# untitled.net
KiCad netlist of a schematic drawn in EAGLE
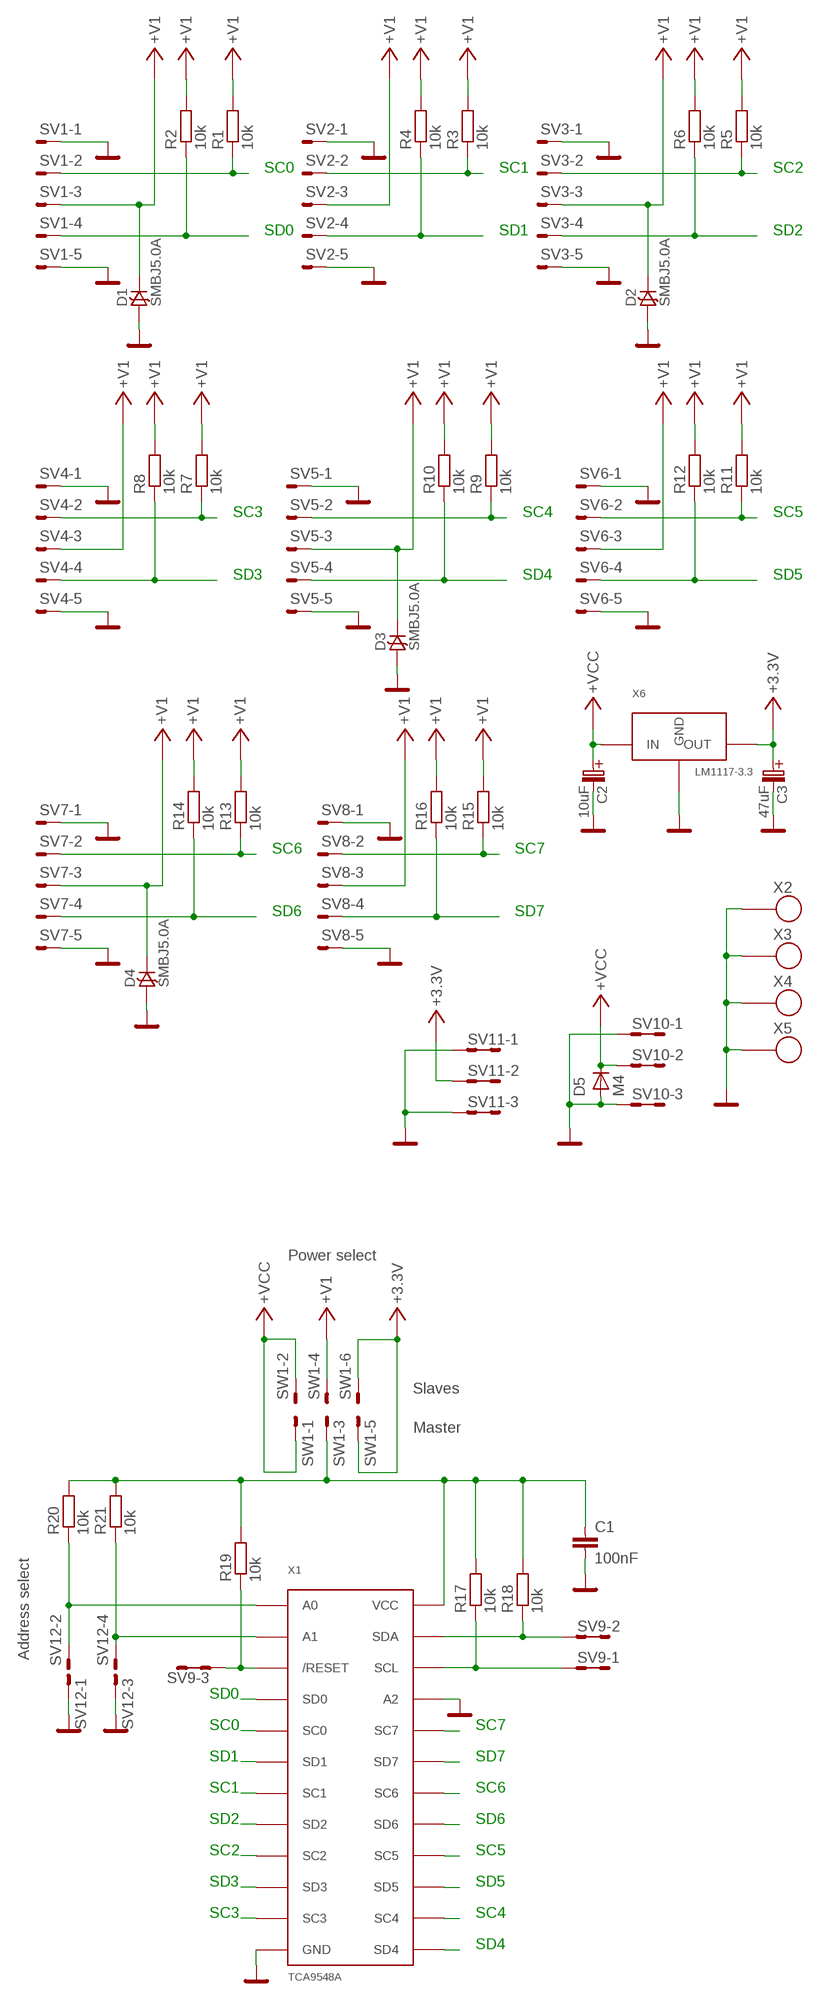
[diagram p0: schematic, sheet 1]

(export (version "E")
  (design (tool "Eeschema 10.0.6"))
  (components
    (comp (ref "C1")
      (value "100nF")
      (footprint "eagle-import:C0805")
      (libsource (lib "eagle-import") (part "C0805"))
    )
    (comp (ref "C2") (value "10uF") (footprint "eagle-import:B") (libsource (lib "eagle-import") (part "B")))
    (comp (ref "C3") (value "47uF") (footprint "eagle-import:C") (libsource (lib "eagle-import") (part "C")))
    (comp (ref "D1")
      (value "SMBJ5.0A")
      (footprint "eagle-import:SMA")
      (libsource (lib "eagle-import") (part "D-TRANSIL-SMA"))
    )
    (comp (ref "D2")
      (value "SMBJ5.0A")
      (footprint "eagle-import:SMA")
      (libsource (lib "eagle-import") (part "D-TRANSIL-SMA"))
    )
    (comp (ref "D3")
      (value "SMBJ5.0A")
      (footprint "eagle-import:SMA")
      (libsource (lib "eagle-import") (part "D-TRANSIL-SMA"))
    )
    (comp (ref "D4")
      (value "SMBJ5.0A")
      (footprint "eagle-import:SMA")
      (libsource (lib "eagle-import") (part "D-TRANSIL-SMA"))
    )
    (comp (ref "D5")
      (value "M4")
      (footprint "eagle-import:SMA")
      (libsource (lib "eagle-import") (part "D-OB.SMA"))
    )
    (comp (ref "R1")
      (value "10k")
      (footprint "eagle-import:0805")
      (libsource (lib "eagle-import") (part "R0805"))
    )
    (comp (ref "R2")
      (value "10k")
      (footprint "eagle-import:0805")
      (libsource (lib "eagle-import") (part "R0805"))
    )
    (comp (ref "R3")
      (value "10k")
      (footprint "eagle-import:0805")
      (libsource (lib "eagle-import") (part "R0805"))
    )
    (comp (ref "R4")
      (value "10k")
      (footprint "eagle-import:0805")
      (libsource (lib "eagle-import") (part "R0805"))
    )
    (comp (ref "R5")
      (value "10k")
      (footprint "eagle-import:0805")
      (libsource (lib "eagle-import") (part "R0805"))
    )
    (comp (ref "R6")
      (value "10k")
      (footprint "eagle-import:0805")
      (libsource (lib "eagle-import") (part "R0805"))
    )
    (comp (ref "R7")
      (value "10k")
      (footprint "eagle-import:0805")
      (libsource (lib "eagle-import") (part "R0805"))
    )
    (comp (ref "R8")
      (value "10k")
      (footprint "eagle-import:0805")
      (libsource (lib "eagle-import") (part "R0805"))
    )
    (comp (ref "R9")
      (value "10k")
      (footprint "eagle-import:0805")
      (libsource (lib "eagle-import") (part "R0805"))
    )
    (comp (ref "R10")
      (value "10k")
      (footprint "eagle-import:0805")
      (libsource (lib "eagle-import") (part "R0805"))
    )
    (comp (ref "R11")
      (value "10k")
      (footprint "eagle-import:0805")
      (libsource (lib "eagle-import") (part "R0805"))
    )
    (comp (ref "R12")
      (value "10k")
      (footprint "eagle-import:0805")
      (libsource (lib "eagle-import") (part "R0805"))
    )
    (comp (ref "R13")
      (value "10k")
      (footprint "eagle-import:0805")
      (libsource (lib "eagle-import") (part "R0805"))
    )
    (comp (ref "R14")
      (value "10k")
      (footprint "eagle-import:0805")
      (libsource (lib "eagle-import") (part "R0805"))
    )
    (comp (ref "R15")
      (value "10k")
      (footprint "eagle-import:0805")
      (libsource (lib "eagle-import") (part "R0805"))
    )
    (comp (ref "R16")
      (value "10k")
      (footprint "eagle-import:0805")
      (libsource (lib "eagle-import") (part "R0805"))
    )
    (comp (ref "R17")
      (value "10k")
      (footprint "eagle-import:0805")
      (libsource (lib "eagle-import") (part "R0805"))
    )
    (comp (ref "R18")
      (value "10k")
      (footprint "eagle-import:0805")
      (libsource (lib "eagle-import") (part "R0805"))
    )
    (comp (ref "R19")
      (value "10k")
      (footprint "eagle-import:0805")
      (libsource (lib "eagle-import") (part "R0805"))
    )
    (comp (ref "R20")
      (value "10k")
      (footprint "eagle-import:0805")
      (libsource (lib "eagle-import") (part "R0805"))
    )
    (comp (ref "R21")
      (value "10k")
      (footprint "eagle-import:0805")
      (libsource (lib "eagle-import") (part "R0805"))
    )
    (comp (ref "SV1")
      (value "MA05-1")
      (footprint "eagle-import:MA05-1")
      (libsource (lib "eagle-import") (part "MA05-1"))
    )
    (comp (ref "SV2")
      (value "MA05-1")
      (footprint "eagle-import:MA05-1")
      (libsource (lib "eagle-import") (part "MA05-1"))
    )
    (comp (ref "SV3")
      (value "MA05-1")
      (footprint "eagle-import:MA05-1")
      (libsource (lib "eagle-import") (part "MA05-1"))
    )
    (comp (ref "SV4")
      (value "MA05-1")
      (footprint "eagle-import:MA05-1")
      (libsource (lib "eagle-import") (part "MA05-1"))
    )
    (comp (ref "SV5")
      (value "MA05-1")
      (footprint "eagle-import:MA05-1")
      (libsource (lib "eagle-import") (part "MA05-1"))
    )
    (comp (ref "SV6")
      (value "MA05-1")
      (footprint "eagle-import:MA05-1")
      (libsource (lib "eagle-import") (part "MA05-1"))
    )
    (comp (ref "SV7")
      (value "MA05-1")
      (footprint "eagle-import:MA05-1")
      (libsource (lib "eagle-import") (part "MA05-1"))
    )
    (comp (ref "SV8")
      (value "MA05-1")
      (footprint "eagle-import:MA05-1")
      (libsource (lib "eagle-import") (part "MA05-1"))
    )
    (comp (ref "SV9")
      (value "MA03-2")
      (footprint "eagle-import:MA03-2")
      (libsource (lib "eagle-import") (part "MA03-2"))
    )
    (comp (ref "SV10")
      (value "MA03-2")
      (footprint "eagle-import:MA03-2")
      (libsource (lib "eagle-import") (part "MA03-2"))
    )
    (comp (ref "SV11")
      (value "MA03-2")
      (footprint "eagle-import:MA03-2")
      (libsource (lib "eagle-import") (part "MA03-2"))
    )
    (comp (ref "SV12")
      (value "MA02-3")
      (footprint "eagle-import:MA02-2")
      (libsource (lib "eagle-import") (part "MA02-3"))
    )
    (comp (ref "SW1")
      (value "MA03-3")
      (footprint "eagle-import:MA03-2")
      (libsource (lib "eagle-import") (part "MA03-3"))
    )
    (comp (ref "X1")
      (value "TCA9548A")
      (footprint "eagle-import:TSS0P24")
      (libsource (lib "eagle-import") (part "TCA9548A"))
    )
    (comp (ref "X2")
      (value "SROUB3M")
      (footprint "eagle-import:SROUB3M")
      (libsource (lib "eagle-import") (part "SROUB3M"))
    )
    (comp (ref "X3")
      (value "SROUB3M")
      (footprint "eagle-import:SROUB3M")
      (libsource (lib "eagle-import") (part "SROUB3M"))
    )
    (comp (ref "X4")
      (value "SROUB3M")
      (footprint "eagle-import:SROUB3M")
      (libsource (lib "eagle-import") (part "SROUB3M"))
    )
    (comp (ref "X5")
      (value "SROUB3M")
      (footprint "eagle-import:SROUB3M")
      (libsource (lib "eagle-import") (part "SROUB3M"))
    )
    (comp (ref "X6")
      (value "LM1117-3.3")
      (footprint "eagle-import:SOT223")
      (libsource (lib "eagle-import") (part "LM1117"))
    )
  )
  (nets
    (net (code "1") (name "+3.3V") (class "Default")
      (node (ref "C3") (pin "+") (pinfunction "C_EL+_+") (pintype "passive"))
      (node (ref "SV11") (pin "3") (pinfunction "K_3") (pintype "passive"))
      (node (ref "SV11") (pin "4") (pinfunction "K_4") (pintype "passive"))
      (node (ref "SW1") (pin "5") (pinfunction "P$1_5") (pintype "passive"))
      (node (ref "SW1") (pin "6") (pinfunction "P$1_6") (pintype "passive"))
      (node (ref "X6") (pin "2") (pinfunction "OUT_2") (pintype "bidirectional"))
      (node (ref "X6") (pin "4") (pinfunction "OUT_4") (pintype "bidirectional"))
    )
    (net (code "2") (name "+V1") (class "Default")
      (node (ref "D1") (pin "K") (pinfunction "K_K") (pintype "passive"))
      (node (ref "D2") (pin "K") (pinfunction "K_K") (pintype "passive"))
      (node (ref "D3") (pin "K") (pinfunction "K_K") (pintype "passive"))
      (node (ref "D4") (pin "K") (pinfunction "K_K") (pintype "passive"))
      (node (ref "R1") (pin "2") (pinfunction "2_2") (pintype "passive"))
      (node (ref "R10") (pin "2") (pinfunction "2_2") (pintype "passive"))
      (node (ref "R11") (pin "2") (pinfunction "2_2") (pintype "passive"))
      (node (ref "R12") (pin "2") (pinfunction "2_2") (pintype "passive"))
      (node (ref "R13") (pin "2") (pinfunction "2_2") (pintype "passive"))
      (node (ref "R14") (pin "2") (pinfunction "2_2") (pintype "passive"))
      (node (ref "R15") (pin "2") (pinfunction "2_2") (pintype "passive"))
      (node (ref "R16") (pin "2") (pinfunction "2_2") (pintype "passive"))
      (node (ref "R2") (pin "2") (pinfunction "2_2") (pintype "passive"))
      (node (ref "R3") (pin "2") (pinfunction "2_2") (pintype "passive"))
      (node (ref "R4") (pin "2") (pinfunction "2_2") (pintype "passive"))
      (node (ref "R5") (pin "2") (pinfunction "2_2") (pintype "passive"))
      (node (ref "R6") (pin "2") (pinfunction "2_2") (pintype "passive"))
      (node (ref "R7") (pin "2") (pinfunction "2_2") (pintype "passive"))
      (node (ref "R8") (pin "2") (pinfunction "2_2") (pintype "passive"))
      (node (ref "R9") (pin "2") (pinfunction "2_2") (pintype "passive"))
      (node (ref "SV1") (pin "3") (pinfunction "P$1_3") (pintype "passive"))
      (node (ref "SV2") (pin "3") (pinfunction "P$1_3") (pintype "passive"))
      (node (ref "SV3") (pin "3") (pinfunction "P$1_3") (pintype "passive"))
      (node (ref "SV4") (pin "3") (pinfunction "P$1_3") (pintype "passive"))
      (node (ref "SV5") (pin "3") (pinfunction "P$1_3") (pintype "passive"))
      (node (ref "SV6") (pin "3") (pinfunction "P$1_3") (pintype "passive"))
      (node (ref "SV7") (pin "3") (pinfunction "P$1_3") (pintype "passive"))
      (node (ref "SV8") (pin "3") (pinfunction "P$1_3") (pintype "passive"))
      (node (ref "SW1") (pin "4") (pinfunction "P$1_4") (pintype "passive"))
    )
    (net (code "3") (name "+VCC") (class "Default")
      (node (ref "C2") (pin "+") (pinfunction "C_EL+_+") (pintype "passive"))
      (node (ref "D5") (pin "K") (pinfunction "C_K") (pintype "passive"))
      (node (ref "SV10") (pin "3") (pinfunction "K_3") (pintype "passive"))
      (node (ref "SV10") (pin "4") (pinfunction "K_4") (pintype "passive"))
      (node (ref "SW1") (pin "1") (pinfunction "P$1_1") (pintype "passive"))
      (node (ref "SW1") (pin "2") (pinfunction "P$1_2") (pintype "passive"))
      (node (ref "X6") (pin "3") (pinfunction "IN_3") (pintype "bidirectional"))
    )
    (net (code "4") (name "/SC0") (class "Default")
      (node (ref "R1") (pin "1") (pinfunction "1_1") (pintype "passive"))
      (node (ref "SV1") (pin "2") (pinfunction "P$1_2") (pintype "passive"))
      (node (ref "X1") (pin "5") (pinfunction "SC0_5") (pintype "bidirectional"))
    )
    (net (code "5") (name "/SC1") (class "Default")
      (node (ref "R3") (pin "1") (pinfunction "1_1") (pintype "passive"))
      (node (ref "SV2") (pin "2") (pinfunction "P$1_2") (pintype "passive"))
      (node (ref "X1") (pin "7") (pinfunction "SC1_7") (pintype "bidirectional"))
    )
    (net (code "6") (name "/SC2") (class "Default")
      (node (ref "R5") (pin "1") (pinfunction "1_1") (pintype "passive"))
      (node (ref "SV3") (pin "2") (pinfunction "P$1_2") (pintype "passive"))
      (node (ref "X1") (pin "9") (pinfunction "SC2_9") (pintype "bidirectional"))
    )
    (net (code "7") (name "/SC3") (class "Default")
      (node (ref "R7") (pin "1") (pinfunction "1_1") (pintype "passive"))
      (node (ref "SV4") (pin "2") (pinfunction "P$1_2") (pintype "passive"))
      (node (ref "X1") (pin "11") (pinfunction "SC3_11") (pintype "bidirectional"))
    )
    (net (code "8") (name "/SC4") (class "Default")
      (node (ref "R9") (pin "1") (pinfunction "1_1") (pintype "passive"))
      (node (ref "SV5") (pin "2") (pinfunction "P$1_2") (pintype "passive"))
      (node (ref "X1") (pin "14") (pinfunction "SC4_14") (pintype "bidirectional"))
    )
    (net (code "9") (name "/SC5") (class "Default")
      (node (ref "R11") (pin "1") (pinfunction "1_1") (pintype "passive"))
      (node (ref "SV6") (pin "2") (pinfunction "P$1_2") (pintype "passive"))
      (node (ref "X1") (pin "16") (pinfunction "SC5_16") (pintype "bidirectional"))
    )
    (net (code "10") (name "/SC6") (class "Default")
      (node (ref "R13") (pin "1") (pinfunction "1_1") (pintype "passive"))
      (node (ref "SV7") (pin "2") (pinfunction "P$1_2") (pintype "passive"))
      (node (ref "X1") (pin "18") (pinfunction "SC6_18") (pintype "bidirectional"))
    )
    (net (code "11") (name "/SC7") (class "Default")
      (node (ref "R15") (pin "1") (pinfunction "1_1") (pintype "passive"))
      (node (ref "SV8") (pin "2") (pinfunction "P$1_2") (pintype "passive"))
      (node (ref "X1") (pin "20") (pinfunction "SC7_20") (pintype "bidirectional"))
    )
    (net (code "12") (name "/SD0") (class "Default")
      (node (ref "R2") (pin "1") (pinfunction "1_1") (pintype "passive"))
      (node (ref "SV1") (pin "4") (pinfunction "P$1_4") (pintype "passive"))
      (node (ref "X1") (pin "4") (pinfunction "SD0_4") (pintype "bidirectional"))
    )
    (net (code "13") (name "/SD1") (class "Default")
      (node (ref "R4") (pin "1") (pinfunction "1_1") (pintype "passive"))
      (node (ref "SV2") (pin "4") (pinfunction "P$1_4") (pintype "passive"))
      (node (ref "X1") (pin "6") (pinfunction "SD1_6") (pintype "bidirectional"))
    )
    (net (code "14") (name "/SD2") (class "Default")
      (node (ref "R6") (pin "1") (pinfunction "1_1") (pintype "passive"))
      (node (ref "SV3") (pin "4") (pinfunction "P$1_4") (pintype "passive"))
      (node (ref "X1") (pin "8") (pinfunction "SD2_8") (pintype "bidirectional"))
    )
    (net (code "15") (name "/SD3") (class "Default")
      (node (ref "R8") (pin "1") (pinfunction "1_1") (pintype "passive"))
      (node (ref "SV4") (pin "4") (pinfunction "P$1_4") (pintype "passive"))
      (node (ref "X1") (pin "10") (pinfunction "SD3_10") (pintype "bidirectional"))
    )
    (net (code "16") (name "/SD4") (class "Default")
      (node (ref "R10") (pin "1") (pinfunction "1_1") (pintype "passive"))
      (node (ref "SV5") (pin "4") (pinfunction "P$1_4") (pintype "passive"))
      (node (ref "X1") (pin "13") (pinfunction "SD4_13") (pintype "bidirectional"))
    )
    (net (code "17") (name "/SD5") (class "Default")
      (node (ref "R12") (pin "1") (pinfunction "1_1") (pintype "passive"))
      (node (ref "SV6") (pin "4") (pinfunction "P$1_4") (pintype "passive"))
      (node (ref "X1") (pin "15") (pinfunction "SD5_15") (pintype "bidirectional"))
    )
    (net (code "18") (name "/SD6") (class "Default")
      (node (ref "R14") (pin "1") (pinfunction "1_1") (pintype "passive"))
      (node (ref "SV7") (pin "4") (pinfunction "P$1_4") (pintype "passive"))
      (node (ref "X1") (pin "17") (pinfunction "SD6_17") (pintype "bidirectional"))
    )
    (net (code "19") (name "/SD7") (class "Default")
      (node (ref "R16") (pin "1") (pinfunction "1_1") (pintype "passive"))
      (node (ref "SV8") (pin "4") (pinfunction "P$1_4") (pintype "passive"))
      (node (ref "X1") (pin "19") (pinfunction "SD7_19") (pintype "bidirectional"))
    )
    (net (code "20") (name "GND") (class "Default")
      (node (ref "C1") (pin "2") (pinfunction "2_2") (pintype "passive"))
      (node (ref "C2") (pin "-") (pinfunction "C_EL-_-") (pintype "passive"))
      (node (ref "C3") (pin "-") (pinfunction "C_EL-_-") (pintype "passive"))
      (node (ref "D1") (pin "A") (pinfunction "A_A") (pintype "passive"))
      (node (ref "D2") (pin "A") (pinfunction "A_A") (pintype "passive"))
      (node (ref "D3") (pin "A") (pinfunction "A_A") (pintype "passive"))
      (node (ref "D4") (pin "A") (pinfunction "A_A") (pintype "passive"))
      (node (ref "D5") (pin "A") (pinfunction "A_A") (pintype "passive"))
      (node (ref "SV1") (pin "1") (pinfunction "P$1_1") (pintype "passive"))
      (node (ref "SV1") (pin "5") (pinfunction "P$1_5") (pintype "passive"))
      (node (ref "SV10") (pin "1") (pinfunction "K_1") (pintype "passive"))
      (node (ref "SV10") (pin "2") (pinfunction "K_2") (pintype "passive"))
      (node (ref "SV10") (pin "5") (pinfunction "K_5") (pintype "passive"))
      (node (ref "SV10") (pin "6") (pinfunction "K_6") (pintype "passive"))
      (node (ref "SV11") (pin "1") (pinfunction "K_1") (pintype "passive"))
      (node (ref "SV11") (pin "2") (pinfunction "K_2") (pintype "passive"))
      (node (ref "SV11") (pin "5") (pinfunction "K_5") (pintype "passive"))
      (node (ref "SV11") (pin "6") (pinfunction "K_6") (pintype "passive"))
      (node (ref "SV12") (pin "1") (pinfunction "P$1_1") (pintype "passive"))
      (node (ref "SV12") (pin "3") (pinfunction "P$1_3") (pintype "passive"))
      (node (ref "SV2") (pin "1") (pinfunction "P$1_1") (pintype "passive"))
      (node (ref "SV2") (pin "5") (pinfunction "P$1_5") (pintype "passive"))
      (node (ref "SV3") (pin "1") (pinfunction "P$1_1") (pintype "passive"))
      (node (ref "SV3") (pin "5") (pinfunction "P$1_5") (pintype "passive"))
      (node (ref "SV4") (pin "1") (pinfunction "P$1_1") (pintype "passive"))
      (node (ref "SV4") (pin "5") (pinfunction "P$1_5") (pintype "passive"))
      (node (ref "SV5") (pin "1") (pinfunction "P$1_1") (pintype "passive"))
      (node (ref "SV5") (pin "5") (pinfunction "P$1_5") (pintype "passive"))
      (node (ref "SV6") (pin "1") (pinfunction "P$1_1") (pintype "passive"))
      (node (ref "SV6") (pin "5") (pinfunction "P$1_5") (pintype "passive"))
      (node (ref "SV7") (pin "1") (pinfunction "P$1_1") (pintype "passive"))
      (node (ref "SV7") (pin "5") (pinfunction "P$1_5") (pintype "passive"))
      (node (ref "SV8") (pin "1") (pinfunction "P$1_1") (pintype "passive"))
      (node (ref "SV8") (pin "5") (pinfunction "P$1_5") (pintype "passive"))
      (node (ref "X1") (pin "12") (pinfunction "GND_12") (pintype "bidirectional"))
      (node (ref "X1") (pin "21") (pinfunction "A2_21") (pintype "bidirectional"))
      (node (ref "X2") (pin "P$1") (pinfunction "P$1_P$1") (pintype "bidirectional"))
      (node (ref "X3") (pin "P$1") (pinfunction "P$1_P$1") (pintype "bidirectional"))
      (node (ref "X4") (pin "P$1") (pinfunction "P$1_P$1") (pintype "bidirectional"))
      (node (ref "X5") (pin "P$1") (pinfunction "P$1_P$1") (pintype "bidirectional"))
      (node (ref "X6") (pin "1") (pinfunction "GND_1") (pintype "bidirectional"))
    )
    (net (code "21") (name "Net-(SV12B-P$1)") (class "Default")
      (node (ref "R20") (pin "1") (pinfunction "1_1") (pintype "passive"))
      (node (ref "SV12") (pin "2") (pinfunction "P$1_2") (pintype "passive"))
      (node (ref "X1") (pin "1") (pinfunction "A0_1") (pintype "bidirectional"))
    )
    (net (code "22") (name "Net-(SV12D-P$1)") (class "Default")
      (node (ref "R21") (pin "1") (pinfunction "1_1") (pintype "passive"))
      (node (ref "SV12") (pin "4") (pinfunction "P$1_4") (pintype "passive"))
      (node (ref "X1") (pin "2") (pinfunction "A1_2") (pintype "bidirectional"))
    )
    (net (code "23") (name "Net-(SW1C-P$1)") (class "Default")
      (node (ref "C1") (pin "1") (pinfunction "1_1") (pintype "passive"))
      (node (ref "R17") (pin "2") (pinfunction "2_2") (pintype "passive"))
      (node (ref "R18") (pin "2") (pinfunction "2_2") (pintype "passive"))
      (node (ref "R19") (pin "2") (pinfunction "2_2") (pintype "passive"))
      (node (ref "R20") (pin "2") (pinfunction "2_2") (pintype "passive"))
      (node (ref "R21") (pin "2") (pinfunction "2_2") (pintype "passive"))
      (node (ref "SW1") (pin "3") (pinfunction "P$1_3") (pintype "passive"))
      (node (ref "X1") (pin "24") (pinfunction "VCC_24") (pintype "bidirectional"))
    )
    (net (code "24") (name "Net-(X1-SCL)") (class "Default")
      (node (ref "R17") (pin "1") (pinfunction "1_1") (pintype "passive"))
      (node (ref "SV9") (pin "1") (pinfunction "K_1") (pintype "passive"))
      (node (ref "SV9") (pin "2") (pinfunction "K_2") (pintype "passive"))
      (node (ref "X1") (pin "22") (pinfunction "SCL_22") (pintype "bidirectional"))
    )
    (net (code "25") (name "Net-(X1-SDA)") (class "Default")
      (node (ref "R18") (pin "1") (pinfunction "1_1") (pintype "passive"))
      (node (ref "SV9") (pin "3") (pinfunction "K_3") (pintype "passive"))
      (node (ref "SV9") (pin "4") (pinfunction "K_4") (pintype "passive"))
      (node (ref "X1") (pin "23") (pinfunction "SDA_23") (pintype "bidirectional"))
    )
    (net (code "26") (name "Net-(X1-{slash}RESET)") (class "Default")
      (node (ref "R19") (pin "1") (pinfunction "1_1") (pintype "passive"))
      (node (ref "SV9") (pin "5") (pinfunction "K_5") (pintype "passive"))
      (node (ref "SV9") (pin "6") (pinfunction "K_6") (pintype "passive"))
      (node (ref "X1") (pin "3") (pinfunction "/RESET_3") (pintype "bidirectional"))
    )
  )
)
